# Center_panel_V1_3.net
KiCad netlist of a schematic drawn in EAGLE
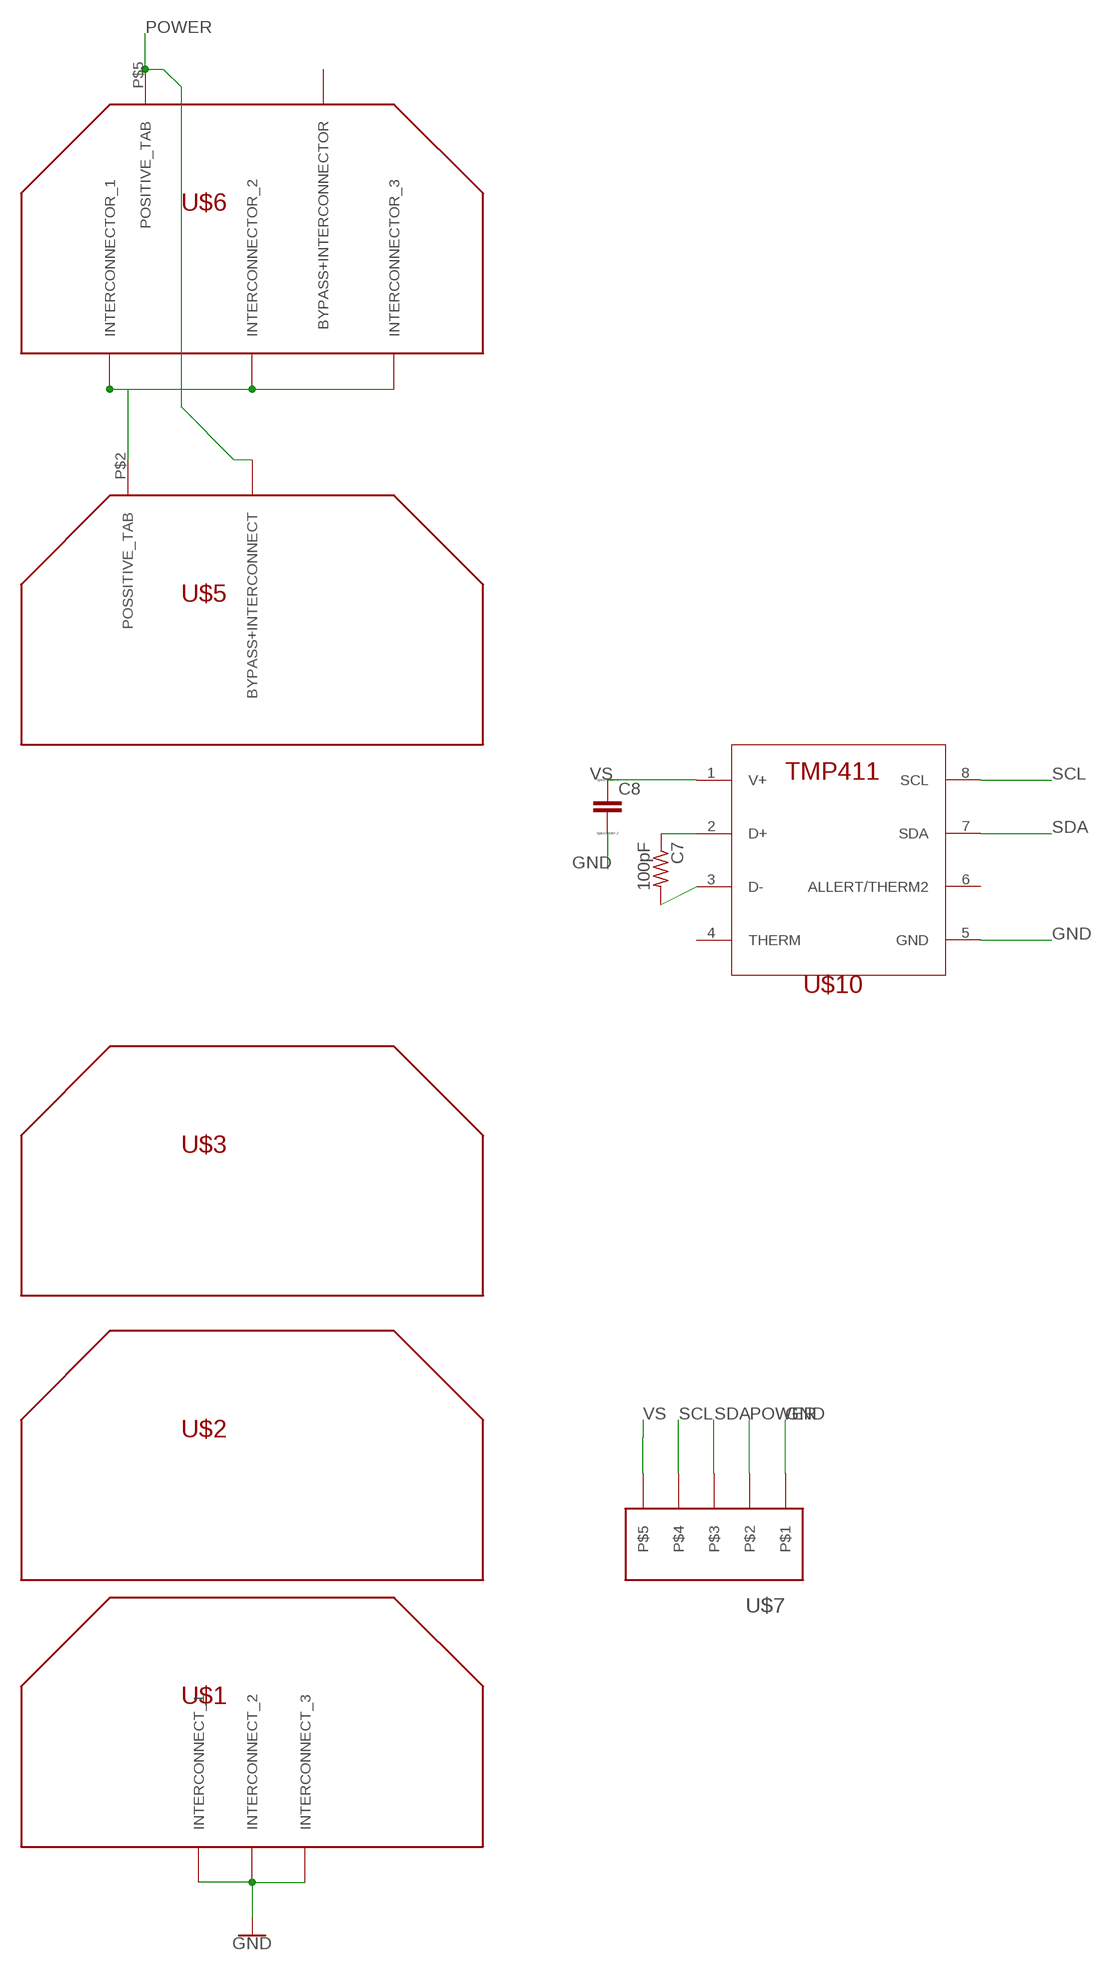
[diagram p0: schematic, sheet 1]

(export (version "E")
  (design (tool "Eeschema 10.0.6"))
  (components
    (comp (ref "C7")
      (value "100pF")
      (footprint "eagle-import:R0805")
      (libsource (lib "eagle-import") (part "R-US_R0805"))
    )
    (comp (ref "C8") (value "C") (footprint "eagle-import:C0805") (libsource (lib "eagle-import") (part "C")))
    (comp (ref "U$1")
      (value "SOLAR_CELL_BOTTOM")
      (footprint "eagle-import:SOLAR_CELL_BOTTOM_SHORT-PADS")
      (libsource (lib "eagle-import") (part "SOLAR_CELL_BOTTOM"))
    )
    (comp (ref "U$2")
      (value "SOALAR_CELL_OUTLINE")
      (footprint "eagle-import:SOLAR_CELL_OUTLINE")
      (libsource (lib "eagle-import") (part "SOALAR_CELL_OUTLINE"))
    )
    (comp (ref "U$3")
      (value "SOALAR_CELL_OUTLINE")
      (footprint "eagle-import:SOLAR_CELL_OUTLINE")
      (libsource (lib "eagle-import") (part "SOALAR_CELL_OUTLINE"))
    )
    (comp (ref "U$5")
      (value "SOLAR_CELL_TOP")
      (footprint "eagle-import:SOLAR_CELL_TOP_SHORT-PAD")
      (libsource (lib "eagle-import") (part "SOLAR_CELL_TOP"))
    )
    (comp (ref "U$6")
      (value "SOLAR_CELL_STAND-ALONE")
      (footprint "eagle-import:SOLAR_CELL_STAND-ALONE")
      (libsource (lib "eagle-import") (part "SOLAR_CELL_STAND-ALONE"))
    )
    (comp (ref "U$7")
      (value "PICOLOCK_5")
      (footprint "eagle-import:PICOLOCK_5")
      (libsource (lib "eagle-import") (part "PICOLOCK_5"))
    )
    (comp (ref "U$10")
      (value "TMP411")
      (footprint "eagle-import:TSSOP-8")
      (libsource (lib "eagle-import") (part "TMP411"))
    )
  )
  (nets
    (net (code "1") (name "/POWER") (class "Default")
      (node (ref "U$5") (pin "P$1") (pinfunction "BYPASS+INTERCONNECT_P$1") (pintype "bidirectional"))
      (node (ref "U$6") (pin "P$5") (pinfunction "POSITIVE_TAB_P$5") (pintype "bidirectional"))
      (node (ref "U$7") (pin "P$2") (pinfunction "P$2_P$2") (pintype "bidirectional"))
    )
    (net (code "2") (name "/SCL") (class "Default")
      (node (ref "U$10") (pin "8") (pinfunction "SCL_8") (pintype "bidirectional"))
      (node (ref "U$7") (pin "P$4") (pinfunction "P$4_P$4") (pintype "bidirectional"))
    )
    (net (code "3") (name "/SDA") (class "Default")
      (node (ref "U$10") (pin "7") (pinfunction "SDA_7") (pintype "bidirectional"))
      (node (ref "U$7") (pin "P$3") (pinfunction "P$3_P$3") (pintype "bidirectional"))
    )
    (net (code "4") (name "/VS") (class "Default")
      (node (ref "C8") (pin "1") (pinfunction "1_1") (pintype "passive"))
      (node (ref "U$10") (pin "1") (pinfunction "V+_1") (pintype "bidirectional"))
      (node (ref "U$7") (pin "P$5") (pinfunction "P$5_P$5") (pintype "bidirectional"))
    )
    (net (code "5") (name "GND") (class "Default")
      (node (ref "C8") (pin "2") (pinfunction "2_2") (pintype "passive"))
      (node (ref "U$1") (pin "P$1") (pinfunction "INTERCONNECT_1_P$1") (pintype "bidirectional"))
      (node (ref "U$1") (pin "P$2") (pinfunction "INTERCONNECT_2_P$2") (pintype "bidirectional"))
      (node (ref "U$1") (pin "P$3") (pinfunction "INTERCONNECT_3_P$3") (pintype "bidirectional"))
      (node (ref "U$10") (pin "5") (pinfunction "GND_5") (pintype "bidirectional"))
      (node (ref "U$7") (pin "P$1") (pinfunction "P$1_P$1") (pintype "bidirectional"))
    )
    (net (code "6") (name "Net-(U$5-POSSITIVE_TAB)") (class "Default")
      (node (ref "U$5") (pin "P$2") (pinfunction "POSSITIVE_TAB_P$2") (pintype "bidirectional"))
      (node (ref "U$6") (pin "P$1") (pinfunction "INTERCONNECTOR_1_P$1") (pintype "bidirectional"))
      (node (ref "U$6") (pin "P$2") (pinfunction "INTERCONNECTOR_2_P$2") (pintype "bidirectional"))
      (node (ref "U$6") (pin "P$3") (pinfunction "INTERCONNECTOR_3_P$3") (pintype "bidirectional"))
    )
    (net (code "7") (name "Net-(U$10-D+)") (class "Default")
      (node (ref "C7") (pin "1") (pinfunction "1_1") (pintype "passive"))
      (node (ref "U$10") (pin "2") (pinfunction "D+_2") (pintype "bidirectional"))
    )
    (net (code "8") (name "Net-(U$10-D-)") (class "Default")
      (node (ref "C7") (pin "2") (pinfunction "2_2") (pintype "passive"))
      (node (ref "U$10") (pin "3") (pinfunction "D-_3") (pintype "bidirectional"))
    )
    (net (code "9") (name "unconnected-(U$6-BYPASS+INTERCONNECTOR-PadP$4)") (class "Default")
      (node (ref "U$6") (pin "P$4") (pinfunction "BYPASS+INTERCONNECTOR_P$4") (pintype "bidirectional"))
    )
    (net (code "10") (name "unconnected-(U$10-ALLERT{slash}THERM2-Pad6)") (class "Default")
      (node (ref "U$10") (pin "6") (pinfunction "ALLERT/THERM2_6") (pintype "bidirectional"))
    )
    (net (code "11") (name "unconnected-(U$10-THERM-Pad4)") (class "Default")
      (node (ref "U$10") (pin "4") (pinfunction "THERM_4") (pintype "bidirectional"))
    )
  )
)
